# top_PCB_mini.net
KiCad netlist of a schematic drawn in EAGLE
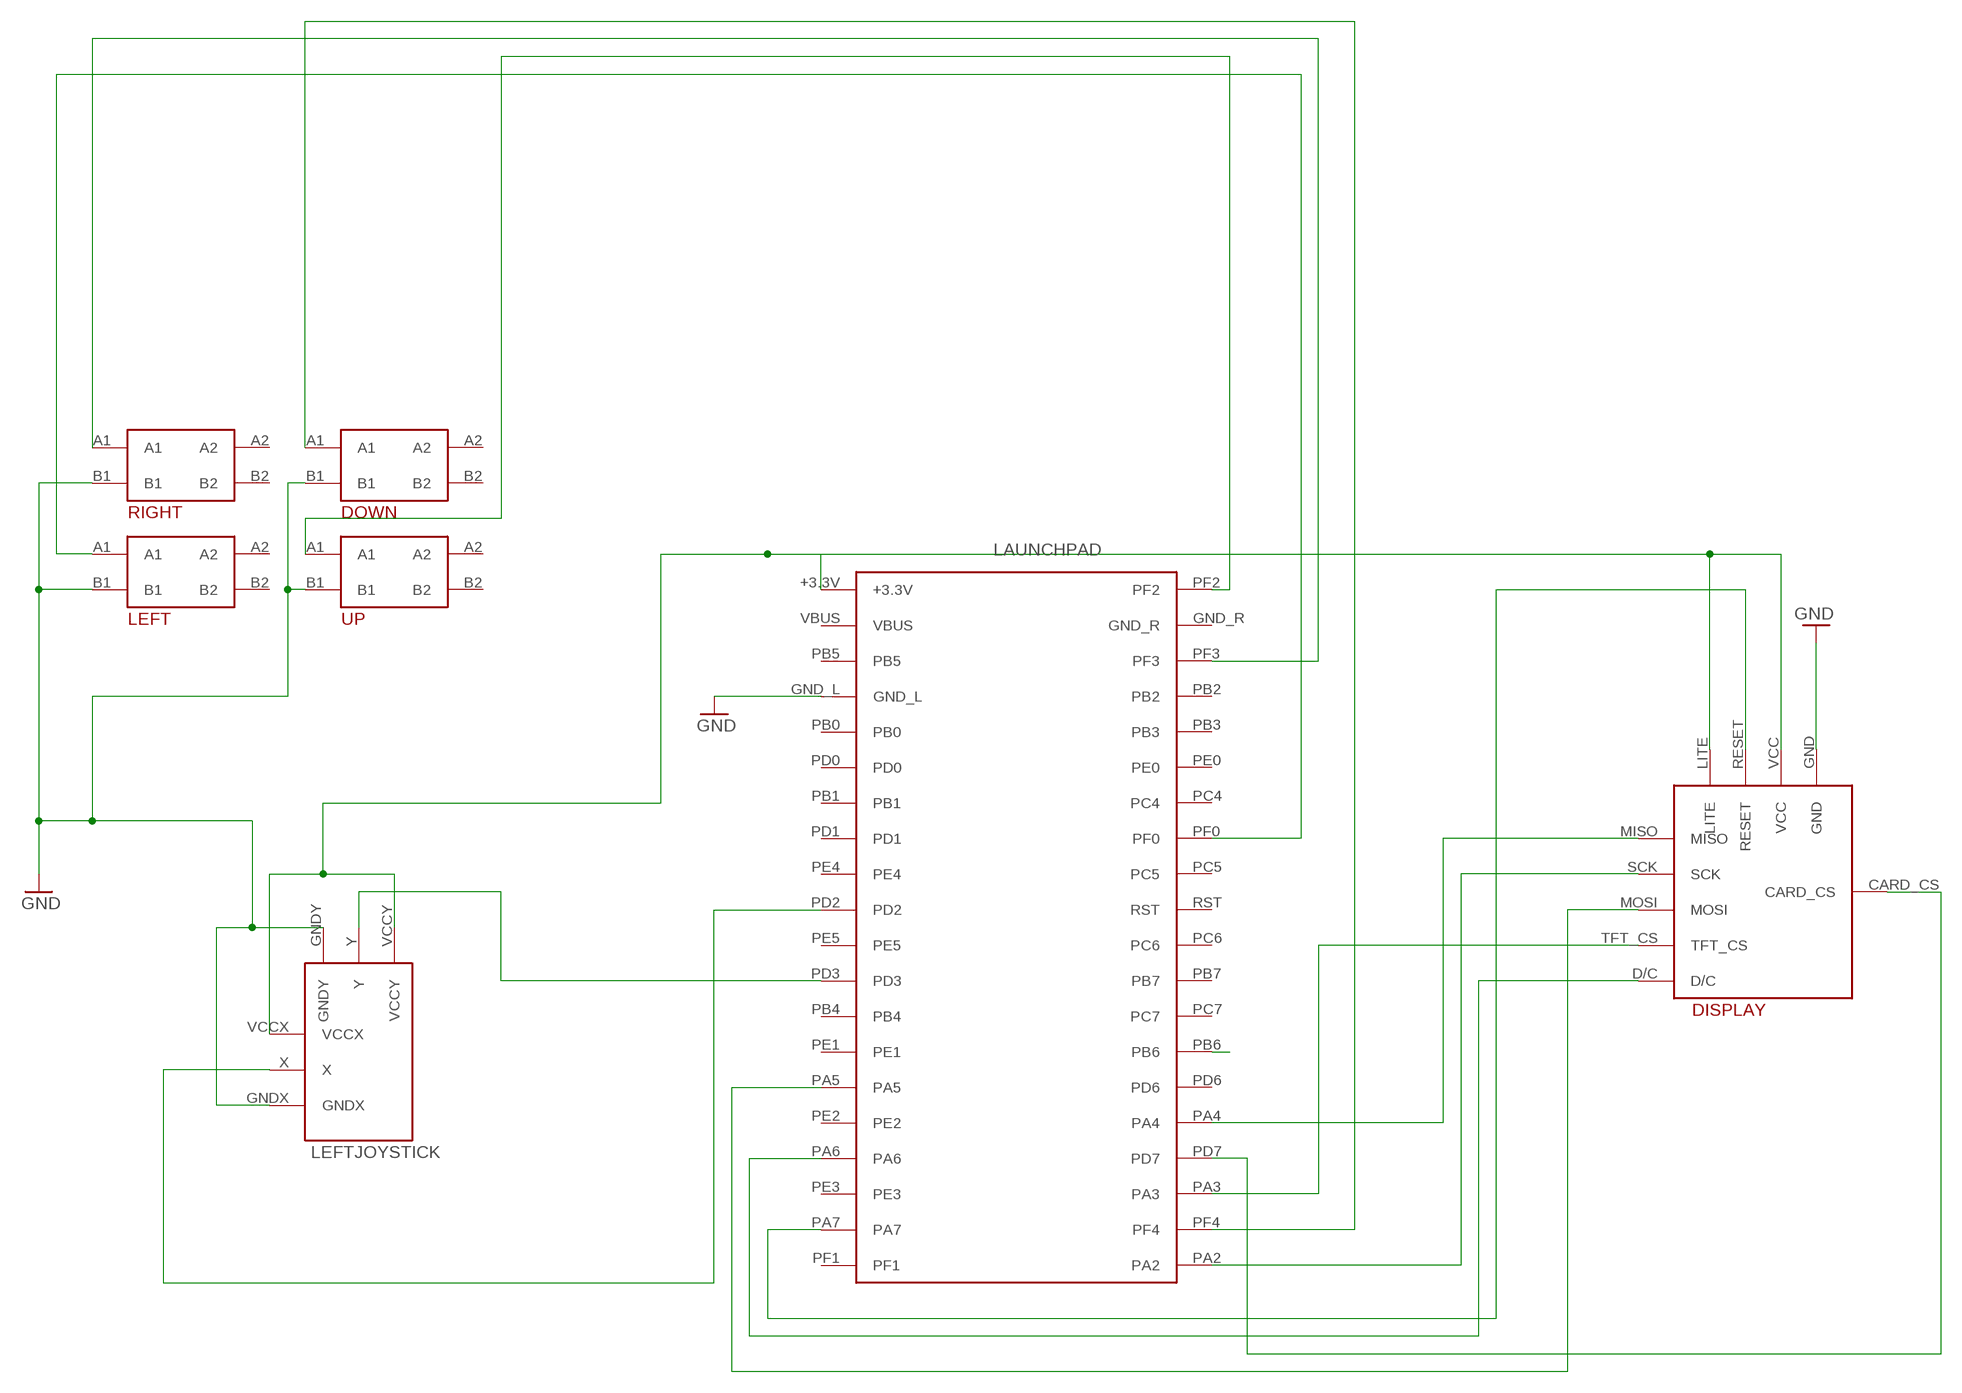
[diagram p0: schematic, sheet 1]

(export (version "E")
  (design (tool "Eeschema 10.0.6"))
  (components
    (comp (ref "DISPLAY")
      (value "ADAFRUITST7735R_18")
      (footprint "eagle-import:ADAFRUITST7735R_18")
      (libsource (lib "eagle-import") (part "ADAFRUITST7735R_18"))
    )
    (comp (ref "DOWN")
      (value "TACTILEBUTTONTHROUGHHOLE")
      (footprint "eagle-import:B3F-40XX-MOD")
      (libsource (lib "eagle-import") (part "TACTILEBUTTONTHROUGHHOLE"))
    )
    (comp (ref "LAUNCHPAD")
      (value "TM4CTM4C")
      (footprint "eagle-import:1_05X2MM")
      (libsource (lib "eagle-import") (part "TM4CTM4C"))
    )
    (comp (ref "LEFT")
      (value "TACTILEBUTTONTHROUGHHOLE")
      (footprint "eagle-import:B3F-40XX-MOD")
      (libsource (lib "eagle-import") (part "TACTILEBUTTONTHROUGHHOLE"))
    )
    (comp (ref "LEFTJOYSTICK")
      (value "JOYSTICKADAFRUIT")
      (footprint "eagle-import:JOYSTICK")
      (libsource (lib "eagle-import") (part "JOYSTICKADAFRUIT"))
    )
    (comp (ref "RIGHT")
      (value "TACTILEBUTTONTHROUGHHOLE")
      (footprint "eagle-import:B3F-40XX-MOD")
      (libsource (lib "eagle-import") (part "TACTILEBUTTONTHROUGHHOLE"))
    )
    (comp (ref "UP")
      (value "TACTILEBUTTONTHROUGHHOLE")
      (footprint "eagle-import:B3F-40XX-MOD")
      (libsource (lib "eagle-import") (part "TACTILEBUTTONTHROUGHHOLE"))
    )
  )
  (nets
    (net (code "1") (name "/GND_R") (class "Default")
      (node (ref "LAUNCHPAD") (pin "GND_R") (pinfunction "GND_R_GND_R") (pintype "power_in"))
    )
    (net (code "2") (name "/VBUS") (class "Default")
      (node (ref "LAUNCHPAD") (pin "VBUS") (pinfunction "VBUS_VBUS") (pintype "power_in"))
    )
    (net (code "3") (name "GND") (class "Default")
      (node (ref "DISPLAY") (pin "GND") (pinfunction "GND_GND") (pintype "bidirectional"))
      (node (ref "DOWN") (pin "B1") (pinfunction "B1_B1") (pintype "bidirectional"))
      (node (ref "LAUNCHPAD") (pin "GND_L") (pinfunction "GND_L_GND_L") (pintype "power_in"))
      (node (ref "LEFT") (pin "B1") (pinfunction "B1_B1") (pintype "bidirectional"))
      (node (ref "LEFTJOYSTICK") (pin "GNDX") (pinfunction "GNDX_GNDX") (pintype "bidirectional"))
      (node (ref "LEFTJOYSTICK") (pin "GNDY") (pinfunction "GNDY_GNDY") (pintype "bidirectional"))
      (node (ref "RIGHT") (pin "B1") (pinfunction "B1_B1") (pintype "bidirectional"))
      (node (ref "UP") (pin "B1") (pinfunction "B1_B1") (pintype "bidirectional"))
    )
    (net (code "4") (name "Net-(DISPLAY-PadCARD_CS)") (class "Default")
      (node (ref "DISPLAY") (pin "CARD_CS") (pinfunction "CARD_CS_CARD_CS") (pintype "bidirectional"))
      (node (ref "LAUNCHPAD") (pin "PD7") (pinfunction "PD7_PD7") (pintype "bidirectional"))
    )
    (net (code "5") (name "Net-(DISPLAY-PadD{slash}C)") (class "Default")
      (node (ref "DISPLAY") (pin "D/C") (pinfunction "D/C_D/C") (pintype "bidirectional"))
      (node (ref "LAUNCHPAD") (pin "PA6") (pinfunction "PA6_PA6") (pintype "bidirectional"))
    )
    (net (code "6") (name "Net-(DISPLAY-PadLITE)") (class "Default")
      (node (ref "DISPLAY") (pin "LITE") (pinfunction "LITE_LITE") (pintype "bidirectional"))
      (node (ref "DISPLAY") (pin "VCC") (pinfunction "VCC_VCC") (pintype "bidirectional"))
      (node (ref "LAUNCHPAD") (pin "+3.3V") (pinfunction "+3.3V_+3.3V") (pintype "power_in"))
      (node (ref "LEFTJOYSTICK") (pin "VCCX") (pinfunction "VCCX_VCCX") (pintype "bidirectional"))
      (node (ref "LEFTJOYSTICK") (pin "VCCY") (pinfunction "VCCY_VCCY") (pintype "bidirectional"))
    )
    (net (code "7") (name "Net-(DISPLAY-PadMISO)") (class "Default")
      (node (ref "DISPLAY") (pin "MISO") (pinfunction "MISO_MISO") (pintype "bidirectional"))
      (node (ref "LAUNCHPAD") (pin "PA4") (pinfunction "PA4_PA4") (pintype "bidirectional"))
    )
    (net (code "8") (name "Net-(DISPLAY-PadMOSI)") (class "Default")
      (node (ref "DISPLAY") (pin "MOSI") (pinfunction "MOSI_MOSI") (pintype "bidirectional"))
      (node (ref "LAUNCHPAD") (pin "PA5") (pinfunction "PA5_PA5") (pintype "bidirectional"))
    )
    (net (code "9") (name "Net-(DISPLAY-PadRESET)") (class "Default")
      (node (ref "DISPLAY") (pin "RESET") (pinfunction "RESET_RESET") (pintype "bidirectional"))
      (node (ref "LAUNCHPAD") (pin "PA7") (pinfunction "PA7_PA7") (pintype "bidirectional"))
    )
    (net (code "10") (name "Net-(DISPLAY-PadSCK)") (class "Default")
      (node (ref "DISPLAY") (pin "SCK") (pinfunction "SCK_SCK") (pintype "bidirectional"))
      (node (ref "LAUNCHPAD") (pin "PA2") (pinfunction "PA2_PA2") (pintype "bidirectional"))
    )
    (net (code "11") (name "Net-(DISPLAY-PadTFT_CS)") (class "Default")
      (node (ref "DISPLAY") (pin "TFT_CS") (pinfunction "TFT_CS_TFT_CS") (pintype "bidirectional"))
      (node (ref "LAUNCHPAD") (pin "PA3") (pinfunction "PA3_PA3") (pintype "bidirectional"))
    )
    (net (code "12") (name "Net-(DOWN-PadA1)") (class "Default")
      (node (ref "DOWN") (pin "A1") (pinfunction "A1_A1") (pintype "bidirectional"))
      (node (ref "LAUNCHPAD") (pin "PF4") (pinfunction "PF4_PF4") (pintype "bidirectional"))
    )
    (net (code "13") (name "Net-(LAUNCHPAD-PadPD2)") (class "Default")
      (node (ref "LAUNCHPAD") (pin "PD2") (pinfunction "PD2_PD2") (pintype "bidirectional"))
      (node (ref "LEFTJOYSTICK") (pin "X") (pinfunction "X_X") (pintype "bidirectional"))
    )
    (net (code "14") (name "Net-(LAUNCHPAD-PadPD3)") (class "Default")
      (node (ref "LAUNCHPAD") (pin "PD3") (pinfunction "PD3_PD3") (pintype "bidirectional"))
      (node (ref "LEFTJOYSTICK") (pin "Y") (pinfunction "Y_Y") (pintype "bidirectional"))
    )
    (net (code "15") (name "Net-(LAUNCHPAD-PadPF0)") (class "Default")
      (node (ref "LAUNCHPAD") (pin "PF0") (pinfunction "PF0_PF0") (pintype "bidirectional"))
      (node (ref "LEFT") (pin "A1") (pinfunction "A1_A1") (pintype "bidirectional"))
    )
    (net (code "16") (name "Net-(LAUNCHPAD-PadPF2)") (class "Default")
      (node (ref "LAUNCHPAD") (pin "PF2") (pinfunction "PF2_PF2") (pintype "bidirectional"))
      (node (ref "UP") (pin "A1") (pinfunction "A1_A1") (pintype "bidirectional"))
    )
    (net (code "17") (name "Net-(LAUNCHPAD-PadPF3)") (class "Default")
      (node (ref "LAUNCHPAD") (pin "PF3") (pinfunction "PF3_PF3") (pintype "bidirectional"))
      (node (ref "RIGHT") (pin "A1") (pinfunction "A1_A1") (pintype "bidirectional"))
    )
    (net (code "18") (name "unconnected-(DOWN-PadA2)") (class "Default")
      (node (ref "DOWN") (pin "A2") (pinfunction "A2_A2") (pintype "bidirectional"))
    )
    (net (code "19") (name "unconnected-(DOWN-PadB2)") (class "Default")
      (node (ref "DOWN") (pin "B2") (pinfunction "B2_B2") (pintype "bidirectional"))
    )
    (net (code "20") (name "unconnected-(LAUNCHPAD-PadPB0)") (class "Default")
      (node (ref "LAUNCHPAD") (pin "PB0") (pinfunction "PB0_PB0") (pintype "bidirectional"))
    )
    (net (code "21") (name "unconnected-(LAUNCHPAD-PadPB1)") (class "Default")
      (node (ref "LAUNCHPAD") (pin "PB1") (pinfunction "PB1_PB1") (pintype "bidirectional"))
    )
    (net (code "22") (name "unconnected-(LAUNCHPAD-PadPB2)") (class "Default")
      (node (ref "LAUNCHPAD") (pin "PB2") (pinfunction "PB2_PB2") (pintype "bidirectional"))
    )
    (net (code "23") (name "unconnected-(LAUNCHPAD-PadPB3)") (class "Default")
      (node (ref "LAUNCHPAD") (pin "PB3") (pinfunction "PB3_PB3") (pintype "bidirectional"))
    )
    (net (code "24") (name "unconnected-(LAUNCHPAD-PadPB4)") (class "Default")
      (node (ref "LAUNCHPAD") (pin "PB4") (pinfunction "PB4_PB4") (pintype "bidirectional"))
    )
    (net (code "25") (name "unconnected-(LAUNCHPAD-PadPB5)") (class "Default")
      (node (ref "LAUNCHPAD") (pin "PB5") (pinfunction "PB5_PB5") (pintype "bidirectional"))
    )
    (net (code "26") (name "unconnected-(LAUNCHPAD-PadPB6)") (class "Default")
      (node (ref "LAUNCHPAD") (pin "PB6") (pinfunction "PB6_PB6") (pintype "bidirectional"))
    )
    (net (code "27") (name "unconnected-(LAUNCHPAD-PadPB7)") (class "Default")
      (node (ref "LAUNCHPAD") (pin "PB7") (pinfunction "PB7_PB7") (pintype "bidirectional"))
    )
    (net (code "28") (name "unconnected-(LAUNCHPAD-PadPC4)") (class "Default")
      (node (ref "LAUNCHPAD") (pin "PC4") (pinfunction "PC4_PC4") (pintype "bidirectional"))
    )
    (net (code "29") (name "unconnected-(LAUNCHPAD-PadPC5)") (class "Default")
      (node (ref "LAUNCHPAD") (pin "PC5") (pinfunction "PC5_PC5") (pintype "bidirectional"))
    )
    (net (code "30") (name "unconnected-(LAUNCHPAD-PadPC6)") (class "Default")
      (node (ref "LAUNCHPAD") (pin "PC6") (pinfunction "PC6_PC6") (pintype "bidirectional"))
    )
    (net (code "31") (name "unconnected-(LAUNCHPAD-PadPC7)") (class "Default")
      (node (ref "LAUNCHPAD") (pin "PC7") (pinfunction "PC7_PC7") (pintype "bidirectional"))
    )
    (net (code "32") (name "unconnected-(LAUNCHPAD-PadPD0)") (class "Default")
      (node (ref "LAUNCHPAD") (pin "PD0") (pinfunction "PD0_PD0") (pintype "bidirectional"))
    )
    (net (code "33") (name "unconnected-(LAUNCHPAD-PadPD1)") (class "Default")
      (node (ref "LAUNCHPAD") (pin "PD1") (pinfunction "PD1_PD1") (pintype "bidirectional"))
    )
    (net (code "34") (name "unconnected-(LAUNCHPAD-PadPD6)") (class "Default")
      (node (ref "LAUNCHPAD") (pin "PD6") (pinfunction "PD6_PD6") (pintype "bidirectional"))
    )
    (net (code "35") (name "unconnected-(LAUNCHPAD-PadPE0)") (class "Default")
      (node (ref "LAUNCHPAD") (pin "PE0") (pinfunction "PE0_PE0") (pintype "bidirectional"))
    )
    (net (code "36") (name "unconnected-(LAUNCHPAD-PadPE1)") (class "Default")
      (node (ref "LAUNCHPAD") (pin "PE1") (pinfunction "PE1_PE1") (pintype "bidirectional"))
    )
    (net (code "37") (name "unconnected-(LAUNCHPAD-PadPE2)") (class "Default")
      (node (ref "LAUNCHPAD") (pin "PE2") (pinfunction "PE2_PE2") (pintype "bidirectional"))
    )
    (net (code "38") (name "unconnected-(LAUNCHPAD-PadPE3)") (class "Default")
      (node (ref "LAUNCHPAD") (pin "PE3") (pinfunction "PE3_PE3") (pintype "bidirectional"))
    )
    (net (code "39") (name "unconnected-(LAUNCHPAD-PadPE4)") (class "Default")
      (node (ref "LAUNCHPAD") (pin "PE4") (pinfunction "PE4_PE4") (pintype "bidirectional"))
    )
    (net (code "40") (name "unconnected-(LAUNCHPAD-PadPE5)") (class "Default")
      (node (ref "LAUNCHPAD") (pin "PE5") (pinfunction "PE5_PE5") (pintype "bidirectional"))
    )
    (net (code "41") (name "unconnected-(LAUNCHPAD-PadPF1)") (class "Default")
      (node (ref "LAUNCHPAD") (pin "PF1") (pinfunction "PF1_PF1") (pintype "bidirectional"))
    )
    (net (code "42") (name "unconnected-(LAUNCHPAD-PadRST)") (class "Default")
      (node (ref "LAUNCHPAD") (pin "RST") (pinfunction "RST_RST") (pintype "bidirectional"))
    )
    (net (code "43") (name "unconnected-(LEFT-PadA2)") (class "Default")
      (node (ref "LEFT") (pin "A2") (pinfunction "A2_A2") (pintype "bidirectional"))
    )
    (net (code "44") (name "unconnected-(LEFT-PadB2)") (class "Default")
      (node (ref "LEFT") (pin "B2") (pinfunction "B2_B2") (pintype "bidirectional"))
    )
    (net (code "45") (name "unconnected-(RIGHT-PadA2)") (class "Default")
      (node (ref "RIGHT") (pin "A2") (pinfunction "A2_A2") (pintype "bidirectional"))
    )
    (net (code "46") (name "unconnected-(RIGHT-PadB2)") (class "Default")
      (node (ref "RIGHT") (pin "B2") (pinfunction "B2_B2") (pintype "bidirectional"))
    )
    (net (code "47") (name "unconnected-(UP-PadA2)") (class "Default")
      (node (ref "UP") (pin "A2") (pinfunction "A2_A2") (pintype "bidirectional"))
    )
    (net (code "48") (name "unconnected-(UP-PadB2)") (class "Default")
      (node (ref "UP") (pin "B2") (pinfunction "B2_B2") (pintype "bidirectional"))
    )
  )
)
